# Schematic.net
KiCad netlist of a schematic drawn in EasyEDA
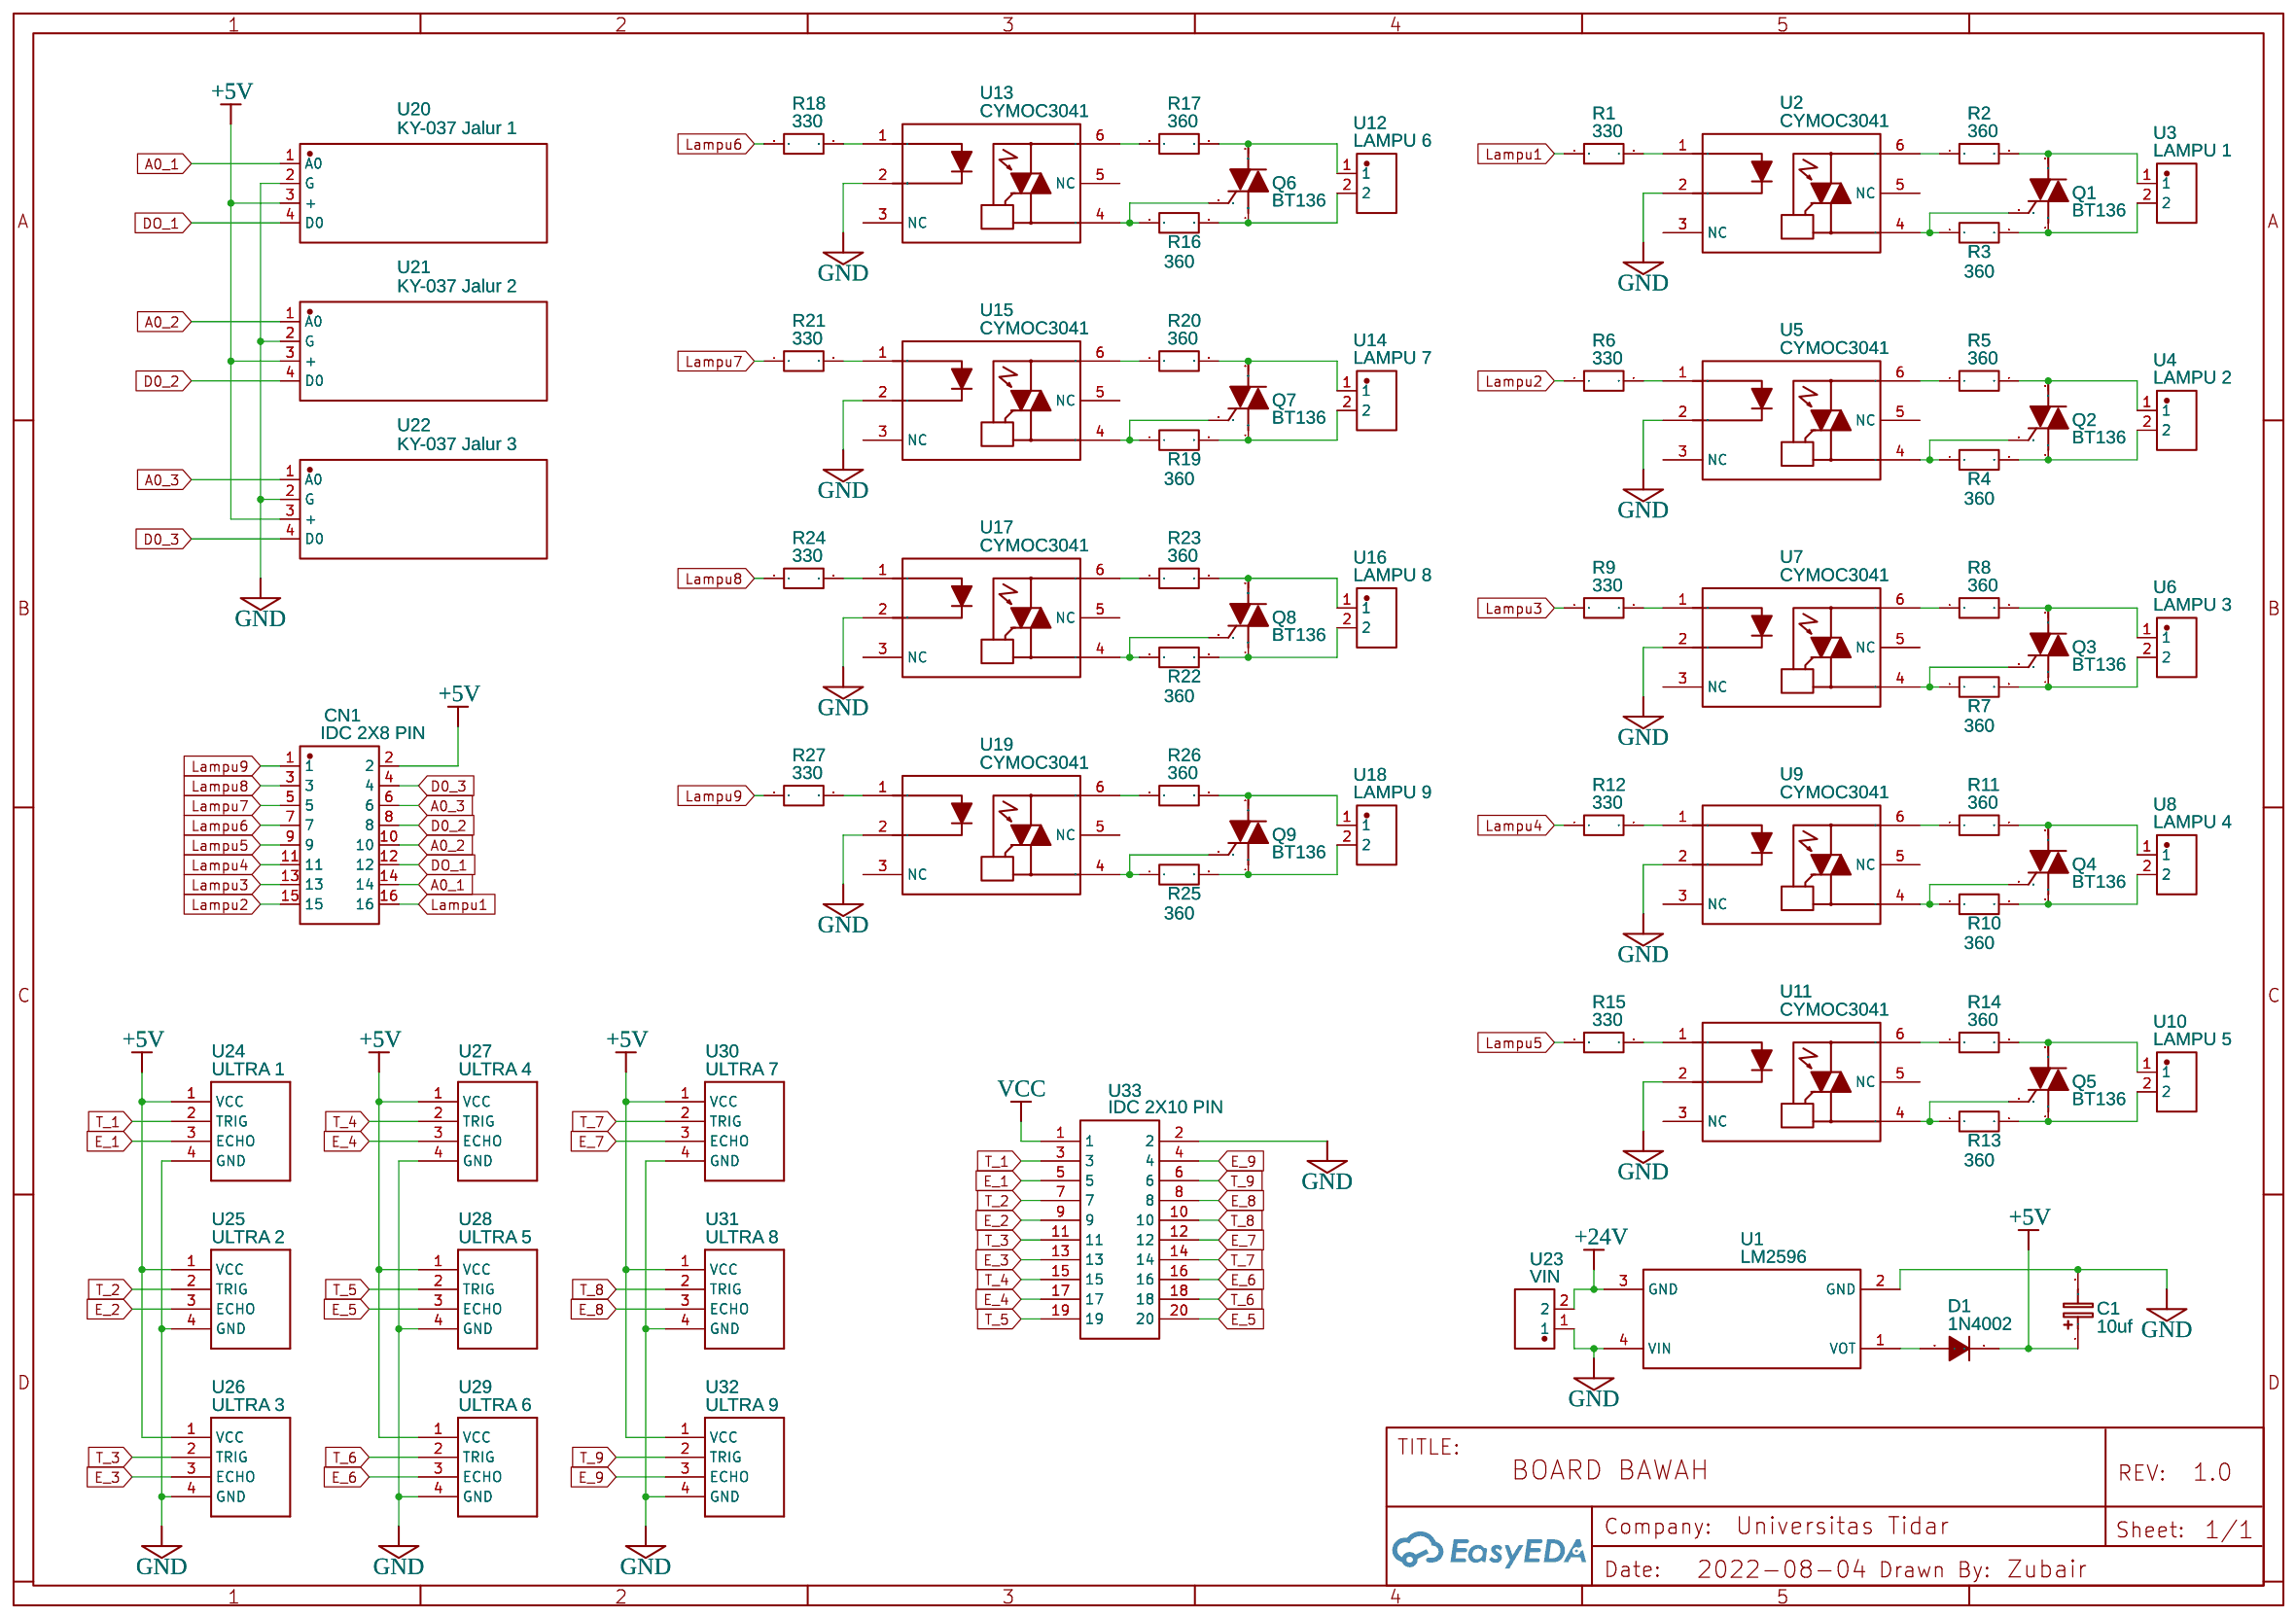
[diagram p0: BOARD BAWAH]
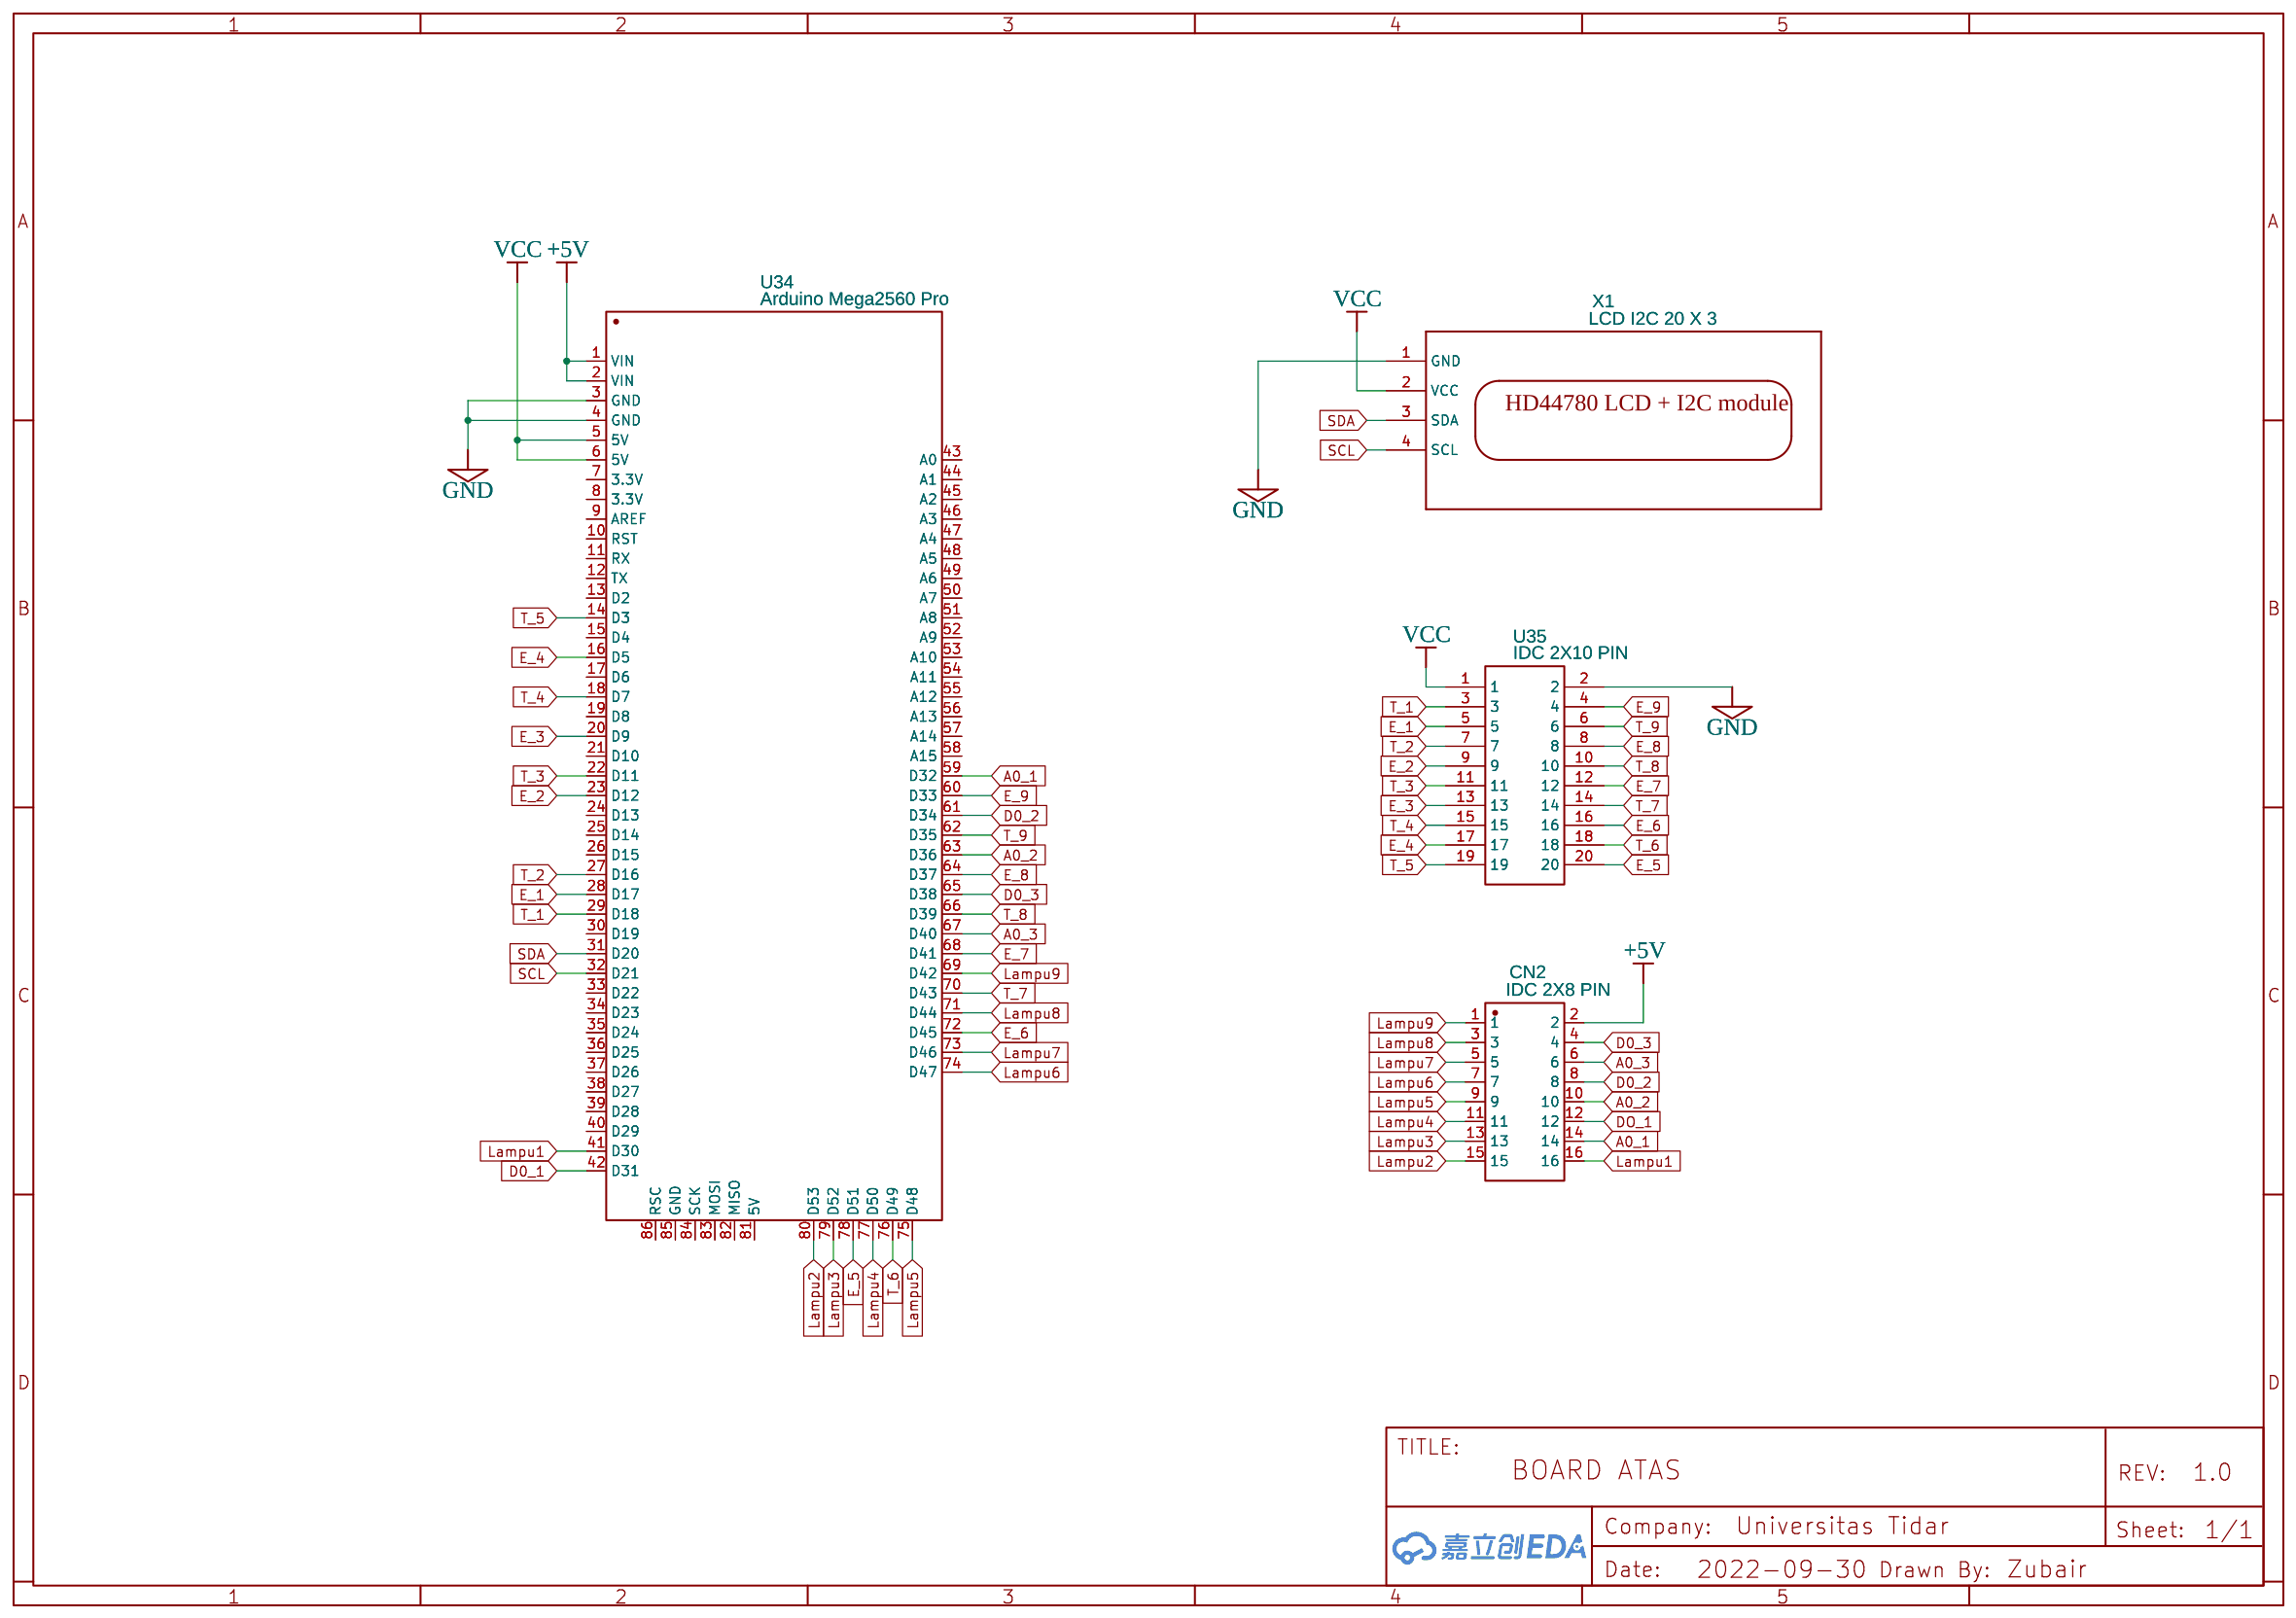
[diagram p1: BOARD ATAS]

(export (version "E")
  (design (tool "Eeschema 10.0.6"))
  (components
    (comp (ref "C1") (value "10uf") (libsource (lib "") (part "CE_TH_D5.0×F2.0_EU")))
    (comp (ref "CN1")
      (value "IDC 2X8 PIN")
      (fields
        (field (name "BOM_Manufacturer Part") "DW254P-2X8-L0")
        (field (name "BOM_Supplier Part") "C4749189")
      )
      (libsource (lib "") (part "DW254P-2X8-L0"))
    )
    (comp (ref "D1") (value "1N4002") (libsource (lib "") (part "1N4002")))
    (comp (ref "Q1")
      (value "BT136")
      (fields (field (name "BOM_Supplier Part") "C98796"))
      (libsource (lib "") (part "BT136"))
    )
    (comp (ref "Q2")
      (value "BT136")
      (fields (field (name "BOM_Supplier Part") "C98796"))
      (libsource (lib "") (part "BT136"))
    )
    (comp (ref "Q3")
      (value "BT136")
      (fields (field (name "BOM_Supplier Part") "C98796"))
      (libsource (lib "") (part "BT136"))
    )
    (comp (ref "Q4")
      (value "BT136")
      (fields (field (name "BOM_Supplier Part") "C98796"))
      (libsource (lib "") (part "BT136"))
    )
    (comp (ref "Q5")
      (value "BT136")
      (fields (field (name "BOM_Supplier Part") "C98796"))
      (libsource (lib "") (part "BT136"))
    )
    (comp (ref "Q6")
      (value "BT136")
      (fields (field (name "BOM_Supplier Part") "C98796"))
      (libsource (lib "") (part "BT136"))
    )
    (comp (ref "Q7")
      (value "BT136")
      (fields (field (name "BOM_Supplier Part") "C98796"))
      (libsource (lib "") (part "BT136"))
    )
    (comp (ref "Q8")
      (value "BT136")
      (fields (field (name "BOM_Supplier Part") "C98796"))
      (libsource (lib "") (part "BT136"))
    )
    (comp (ref "Q9")
      (value "BT136")
      (fields (field (name "BOM_Supplier Part") "C98796"))
      (libsource (lib "") (part "BT136"))
    )
    (comp (ref "R1")
      (value "330")
      (fields
        (field (name "BOM_Manufacturer Part") "贴片电阻ChipResistors")
        (field (name "BOM_Supplier Part") "C9900014833")
      )
      (libsource (lib "") (part "贴片电阻CHIPRESISTORS"))
    )
    (comp (ref "R2")
      (value "360")
      (fields
        (field (name "BOM_Manufacturer Part") "贴片电阻ChipResistors")
        (field (name "BOM_Supplier Part") "C9900014833")
      )
      (libsource (lib "") (part "贴片电阻CHIPRESISTORS"))
    )
    (comp (ref "R3")
      (value "360")
      (fields
        (field (name "BOM_Manufacturer Part") "贴片电阻ChipResistors")
        (field (name "BOM_Supplier Part") "C9900014833")
      )
      (libsource (lib "") (part "贴片电阻CHIPRESISTORS"))
    )
    (comp (ref "R4")
      (value "360")
      (fields
        (field (name "BOM_Manufacturer Part") "贴片电阻ChipResistors")
        (field (name "BOM_Supplier Part") "C9900014833")
      )
      (libsource (lib "") (part "贴片电阻CHIPRESISTORS"))
    )
    (comp (ref "R5")
      (value "360")
      (fields
        (field (name "BOM_Manufacturer Part") "贴片电阻ChipResistors")
        (field (name "BOM_Supplier Part") "C9900014833")
      )
      (libsource (lib "") (part "贴片电阻CHIPRESISTORS"))
    )
    (comp (ref "R6")
      (value "330")
      (fields
        (field (name "BOM_Manufacturer Part") "贴片电阻ChipResistors")
        (field (name "BOM_Supplier Part") "C9900014833")
      )
      (libsource (lib "") (part "贴片电阻CHIPRESISTORS"))
    )
    (comp (ref "R7")
      (value "360")
      (fields
        (field (name "BOM_Manufacturer Part") "贴片电阻ChipResistors")
        (field (name "BOM_Supplier Part") "C9900014833")
      )
      (libsource (lib "") (part "贴片电阻CHIPRESISTORS"))
    )
    (comp (ref "R8")
      (value "360")
      (fields
        (field (name "BOM_Manufacturer Part") "贴片电阻ChipResistors")
        (field (name "BOM_Supplier Part") "C9900014833")
      )
      (libsource (lib "") (part "贴片电阻CHIPRESISTORS"))
    )
    (comp (ref "R9")
      (value "330")
      (fields
        (field (name "BOM_Manufacturer Part") "贴片电阻ChipResistors")
        (field (name "BOM_Supplier Part") "C9900014833")
      )
      (libsource (lib "") (part "贴片电阻CHIPRESISTORS"))
    )
    (comp (ref "R10")
      (value "360")
      (fields
        (field (name "BOM_Manufacturer Part") "贴片电阻ChipResistors")
        (field (name "BOM_Supplier Part") "C9900014833")
      )
      (libsource (lib "") (part "贴片电阻CHIPRESISTORS"))
    )
    (comp (ref "R11")
      (value "360")
      (fields
        (field (name "BOM_Manufacturer Part") "贴片电阻ChipResistors")
        (field (name "BOM_Supplier Part") "C9900014833")
      )
      (libsource (lib "") (part "贴片电阻CHIPRESISTORS"))
    )
    (comp (ref "R12")
      (value "330")
      (fields
        (field (name "BOM_Manufacturer Part") "贴片电阻ChipResistors")
        (field (name "BOM_Supplier Part") "C9900014833")
      )
      (libsource (lib "") (part "贴片电阻CHIPRESISTORS"))
    )
    (comp (ref "R13")
      (value "360")
      (fields
        (field (name "BOM_Manufacturer Part") "贴片电阻ChipResistors")
        (field (name "BOM_Supplier Part") "C9900014833")
      )
      (libsource (lib "") (part "贴片电阻CHIPRESISTORS"))
    )
    (comp (ref "R14")
      (value "360")
      (fields
        (field (name "BOM_Manufacturer Part") "贴片电阻ChipResistors")
        (field (name "BOM_Supplier Part") "C9900014833")
      )
      (libsource (lib "") (part "贴片电阻CHIPRESISTORS"))
    )
    (comp (ref "R15")
      (value "330")
      (fields
        (field (name "BOM_Manufacturer Part") "贴片电阻ChipResistors")
        (field (name "BOM_Supplier Part") "C9900014833")
      )
      (libsource (lib "") (part "贴片电阻CHIPRESISTORS"))
    )
    (comp (ref "R16")
      (value "360")
      (fields
        (field (name "BOM_Manufacturer Part") "贴片电阻ChipResistors")
        (field (name "BOM_Supplier Part") "C9900014833")
      )
      (libsource (lib "") (part "贴片电阻CHIPRESISTORS"))
    )
    (comp (ref "R17")
      (value "360")
      (fields
        (field (name "BOM_Manufacturer Part") "贴片电阻ChipResistors")
        (field (name "BOM_Supplier Part") "C9900014833")
      )
      (libsource (lib "") (part "贴片电阻CHIPRESISTORS"))
    )
    (comp (ref "R18")
      (value "330")
      (fields
        (field (name "BOM_Manufacturer Part") "贴片电阻ChipResistors")
        (field (name "BOM_Supplier Part") "C9900014833")
      )
      (libsource (lib "") (part "贴片电阻CHIPRESISTORS"))
    )
    (comp (ref "R19")
      (value "360")
      (fields
        (field (name "BOM_Manufacturer Part") "贴片电阻ChipResistors")
        (field (name "BOM_Supplier Part") "C9900014833")
      )
      (libsource (lib "") (part "贴片电阻CHIPRESISTORS"))
    )
    (comp (ref "R20")
      (value "360")
      (fields
        (field (name "BOM_Manufacturer Part") "贴片电阻ChipResistors")
        (field (name "BOM_Supplier Part") "C9900014833")
      )
      (libsource (lib "") (part "贴片电阻CHIPRESISTORS"))
    )
    (comp (ref "R21")
      (value "330")
      (fields
        (field (name "BOM_Manufacturer Part") "贴片电阻ChipResistors")
        (field (name "BOM_Supplier Part") "C9900014833")
      )
      (libsource (lib "") (part "贴片电阻CHIPRESISTORS"))
    )
    (comp (ref "R22")
      (value "360")
      (fields
        (field (name "BOM_Manufacturer Part") "贴片电阻ChipResistors")
        (field (name "BOM_Supplier Part") "C9900014833")
      )
      (libsource (lib "") (part "贴片电阻CHIPRESISTORS"))
    )
    (comp (ref "R23")
      (value "360")
      (fields
        (field (name "BOM_Manufacturer Part") "贴片电阻ChipResistors")
        (field (name "BOM_Supplier Part") "C9900014833")
      )
      (libsource (lib "") (part "贴片电阻CHIPRESISTORS"))
    )
    (comp (ref "R24")
      (value "330")
      (fields
        (field (name "BOM_Manufacturer Part") "贴片电阻ChipResistors")
        (field (name "BOM_Supplier Part") "C9900014833")
      )
      (libsource (lib "") (part "贴片电阻CHIPRESISTORS"))
    )
    (comp (ref "R25")
      (value "360")
      (fields
        (field (name "BOM_Manufacturer Part") "贴片电阻ChipResistors")
        (field (name "BOM_Supplier Part") "C9900014833")
      )
      (libsource (lib "") (part "贴片电阻CHIPRESISTORS"))
    )
    (comp (ref "R26")
      (value "360")
      (fields
        (field (name "BOM_Manufacturer Part") "贴片电阻ChipResistors")
        (field (name "BOM_Supplier Part") "C9900014833")
      )
      (libsource (lib "") (part "贴片电阻CHIPRESISTORS"))
    )
    (comp (ref "R27")
      (value "330")
      (fields
        (field (name "BOM_Manufacturer Part") "贴片电阻ChipResistors")
        (field (name "BOM_Supplier Part") "C9900014833")
      )
      (libsource (lib "") (part "贴片电阻CHIPRESISTORS"))
    )
    (comp (ref "U1") (value "LM2596") (libsource (lib "") (part "LM2596")))
    (comp (ref "U2")
      (value "CYMOC3041")
      (fields (field (name "BOM_Supplier Part") "C3018797"))
      (libsource (lib "") (part "CYMOC3041"))
    )
    (comp (ref "U3")
      (value "LAMPU 1")
      (fields
        (field (name "BOM_Manufacturer Part") "DB128V-7.62-2P-GN-S")
        (field (name "BOM_Supplier Part") "C2686074")
      )
      (libsource (lib "") (part "DB128V-7.62-2P-GN-S"))
    )
    (comp (ref "U4")
      (value "LAMPU 2")
      (fields
        (field (name "BOM_Manufacturer Part") "DB128V-7.62-2P-GN-S")
        (field (name "BOM_Supplier Part") "C2686074")
      )
      (libsource (lib "") (part "DB128V-7.62-2P-GN-S"))
    )
    (comp (ref "U5")
      (value "CYMOC3041")
      (fields (field (name "BOM_Supplier Part") "C3018797"))
      (libsource (lib "") (part "CYMOC3041"))
    )
    (comp (ref "U6")
      (value "LAMPU 3")
      (fields
        (field (name "BOM_Manufacturer Part") "DB128V-7.62-2P-GN-S")
        (field (name "BOM_Supplier Part") "C2686074")
      )
      (libsource (lib "") (part "DB128V-7.62-2P-GN-S"))
    )
    (comp (ref "U7")
      (value "CYMOC3041")
      (fields (field (name "BOM_Supplier Part") "C3018797"))
      (libsource (lib "") (part "CYMOC3041"))
    )
    (comp (ref "U8")
      (value "LAMPU 4")
      (fields
        (field (name "BOM_Manufacturer Part") "DB128V-7.62-2P-GN-S")
        (field (name "BOM_Supplier Part") "C2686074")
      )
      (libsource (lib "") (part "DB128V-7.62-2P-GN-S"))
    )
    (comp (ref "U9")
      (value "CYMOC3041")
      (fields (field (name "BOM_Supplier Part") "C3018797"))
      (libsource (lib "") (part "CYMOC3041"))
    )
    (comp (ref "U10")
      (value "LAMPU 5")
      (fields
        (field (name "BOM_Manufacturer Part") "DB128V-7.62-2P-GN-S")
        (field (name "BOM_Supplier Part") "C2686074")
      )
      (libsource (lib "") (part "DB128V-7.62-2P-GN-S"))
    )
    (comp (ref "U11")
      (value "CYMOC3041")
      (fields (field (name "BOM_Supplier Part") "C3018797"))
      (libsource (lib "") (part "CYMOC3041"))
    )
    (comp (ref "U12")
      (value "LAMPU 6")
      (fields
        (field (name "BOM_Manufacturer Part") "DB128V-7.62-2P-GN-S")
        (field (name "BOM_Supplier Part") "C2686074")
      )
      (libsource (lib "") (part "DB128V-7.62-2P-GN-S"))
    )
    (comp (ref "U13")
      (value "CYMOC3041")
      (fields (field (name "BOM_Supplier Part") "C3018797"))
      (libsource (lib "") (part "CYMOC3041"))
    )
    (comp (ref "U14")
      (value "LAMPU 7")
      (fields
        (field (name "BOM_Manufacturer Part") "DB128V-7.62-2P-GN-S")
        (field (name "BOM_Supplier Part") "C2686074")
      )
      (libsource (lib "") (part "DB128V-7.62-2P-GN-S"))
    )
    (comp (ref "U15")
      (value "CYMOC3041")
      (fields (field (name "BOM_Supplier Part") "C3018797"))
      (libsource (lib "") (part "CYMOC3041"))
    )
    (comp (ref "U16")
      (value "LAMPU 8")
      (fields
        (field (name "BOM_Manufacturer Part") "DB128V-7.62-2P-GN-S")
        (field (name "BOM_Supplier Part") "C2686074")
      )
      (libsource (lib "") (part "DB128V-7.62-2P-GN-S"))
    )
    (comp (ref "U17")
      (value "CYMOC3041")
      (fields (field (name "BOM_Supplier Part") "C3018797"))
      (libsource (lib "") (part "CYMOC3041"))
    )
    (comp (ref "U18")
      (value "LAMPU 9")
      (fields
        (field (name "BOM_Manufacturer Part") "DB128V-7.62-2P-GN-S")
        (field (name "BOM_Supplier Part") "C2686074")
      )
      (libsource (lib "") (part "DB128V-7.62-2P-GN-S"))
    )
    (comp (ref "U19")
      (value "CYMOC3041")
      (fields (field (name "BOM_Supplier Part") "C3018797"))
      (libsource (lib "") (part "CYMOC3041"))
    )
    (comp (ref "U20")
      (value "KY-037 Jalur 1")
      (fields (field (name "BOM_Supplier Part") "420301"))
      (libsource (lib "") (part "KY-037 Geräuschsensor"))
    )
    (comp (ref "U21")
      (value "KY-037 Jalur 2")
      (fields (field (name "BOM_Supplier Part") "420301"))
      (libsource (lib "") (part "KY-037 Geräuschsensor"))
    )
    (comp (ref "U22")
      (value "KY-037 Jalur 3")
      (fields (field (name "BOM_Supplier Part") "420301"))
      (libsource (lib "") (part "KY-037 Geräuschsensor"))
    )
    (comp (ref "U23")
      (value "VIN")
      (fields
        (field (name "BOM_Manufacturer Part") "DB128V-7.62-2P-GN-S")
        (field (name "BOM_Supplier Part") "C2686074")
      )
      (libsource (lib "") (part "DB128V-7.62-2P-GN-S_1"))
    )
    (comp (ref "U24") (value "ULTRA 1") (libsource (lib "") (part "ULTRASONIC-HC-SR04 COPY")))
    (comp (ref "U25") (value "ULTRA 2") (libsource (lib "") (part "ULTRASONIC-HC-SR04 COPY")))
    (comp (ref "U26") (value "ULTRA 3") (libsource (lib "") (part "ULTRASONIC-HC-SR04 COPY")))
    (comp (ref "U27") (value "ULTRA 4") (libsource (lib "") (part "ULTRASONIC-HC-SR04 COPY")))
    (comp (ref "U28") (value "ULTRA 5") (libsource (lib "") (part "ULTRASONIC-HC-SR04 COPY")))
    (comp (ref "U29") (value "ULTRA 6") (libsource (lib "") (part "ULTRASONIC-HC-SR04 COPY")))
    (comp (ref "U30") (value "ULTRA 7") (libsource (lib "") (part "ULTRASONIC-HC-SR04 COPY")))
    (comp (ref "U31") (value "ULTRA 8") (libsource (lib "") (part "ULTRASONIC-HC-SR04 COPY")))
    (comp (ref "U32") (value "ULTRA 9") (libsource (lib "") (part "ULTRASONIC-HC-SR04 COPY")))
    (comp (ref "U33")
      (value "IDC 2X10 PIN")
      (fields
        (field (name "BOM_Manufacturer Part") "2*10P牛角插座")
        (field (name "BOM_Supplier Part") "C9900014220")
      )
      (libsource (lib "") (part "2*10P牛角插座"))
    )
    (comp (ref "CN2")
      (value "IDC 2X8 PIN")
      (fields
        (field (name "BOM_Manufacturer Part") "DW254P-2X8-L0")
        (field (name "BOM_Supplier Part") "C4749189")
      )
      (libsource (lib "") (part "DW254P-2X8-L0"))
    )
    (comp (ref "U34") (value "Arduino Mega2560 Pro") (libsource (lib "") (part "Arduino Mega2560 Pro")))
    (comp (ref "U35")
      (value "IDC 2X10 PIN")
      (fields
        (field (name "BOM_Manufacturer Part") "2*10P牛角插座")
        (field (name "BOM_Supplier Part") "C9900014220")
      )
      (libsource (lib "") (part "2*10P牛角插座"))
    )
    (comp (ref "X1")
      (value "LCD I2C 20 X 3")
      (libsource (lib "") (part "SCREEN LCD HD44780LCD WITH I2C MODULE"))
    )
  )
  (nets
    (net (code "1") (name "+5V") (class "Default")
      (node (ref "C1") (pin "1") (pinfunction "1_1") (pintype "unspecified"))
      (node (ref "CN1") (pin "2") (pinfunction "2_2") (pintype "unspecified"))
      (node (ref "CN2") (pin "2") (pinfunction "2_2") (pintype "unspecified"))
      (node (ref "D1") (pin "1") (pinfunction "K_1") (pintype "unspecified"))
      (node (ref "U20") (pin "3") (pinfunction "+_3") (pintype "unspecified"))
      (node (ref "U21") (pin "3") (pinfunction "+_3") (pintype "unspecified"))
      (node (ref "U22") (pin "3") (pinfunction "+_3") (pintype "unspecified"))
      (node (ref "U24") (pin "1") (pinfunction "VCC_1") (pintype "passive"))
      (node (ref "U25") (pin "1") (pinfunction "VCC_1") (pintype "passive"))
      (node (ref "U26") (pin "1") (pinfunction "VCC_1") (pintype "passive"))
      (node (ref "U27") (pin "1") (pinfunction "VCC_1") (pintype "passive"))
      (node (ref "U28") (pin "1") (pinfunction "VCC_1") (pintype "passive"))
      (node (ref "U29") (pin "1") (pinfunction "VCC_1") (pintype "passive"))
      (node (ref "U30") (pin "1") (pinfunction "VCC_1") (pintype "passive"))
      (node (ref "U31") (pin "1") (pinfunction "VCC_1") (pintype "passive"))
      (node (ref "U32") (pin "1") (pinfunction "VCC_1") (pintype "passive"))
      (node (ref "U34") (pin "1") (pinfunction "VIN_1") (pintype "unspecified"))
      (node (ref "U34") (pin "2") (pinfunction "VIN_2") (pintype "unspecified"))
    )
    (net (code "2") (name "+24V") (class "Default")
      (node (ref "U1") (pin "3") (pinfunction "GND_3") (pintype "unspecified"))
      (node (ref "U23") (pin "2") (pinfunction "2_2") (pintype "unspecified"))
    )
    (net (code "3") (name "A0_1") (class "Default")
      (node (ref "CN1") (pin "14") (pinfunction "14_14") (pintype "unspecified"))
      (node (ref "CN2") (pin "14") (pinfunction "14_14") (pintype "unspecified"))
      (node (ref "U20") (pin "1") (pinfunction "A0_1") (pintype "unspecified"))
      (node (ref "U34") (pin "59") (pinfunction "D32_59") (pintype "unspecified"))
    )
    (net (code "4") (name "A0_2") (class "Default")
      (node (ref "CN1") (pin "10") (pinfunction "10_10") (pintype "unspecified"))
      (node (ref "CN2") (pin "10") (pinfunction "10_10") (pintype "unspecified"))
      (node (ref "U21") (pin "1") (pinfunction "A0_1") (pintype "unspecified"))
      (node (ref "U34") (pin "63") (pinfunction "D36_63") (pintype "unspecified"))
    )
    (net (code "5") (name "A0_3") (class "Default")
      (node (ref "CN1") (pin "6") (pinfunction "6_6") (pintype "unspecified"))
      (node (ref "CN2") (pin "6") (pinfunction "6_6") (pintype "unspecified"))
      (node (ref "U22") (pin "1") (pinfunction "A0_1") (pintype "unspecified"))
      (node (ref "U34") (pin "67") (pinfunction "D40_67") (pintype "unspecified"))
    )
    (net (code "6") (name "D0_1") (class "Default")
      (node (ref "U34") (pin "42") (pinfunction "D31_42") (pintype "unspecified"))
    )
    (net (code "7") (name "D0_2") (class "Default")
      (node (ref "CN1") (pin "8") (pinfunction "8_8") (pintype "unspecified"))
      (node (ref "CN2") (pin "8") (pinfunction "8_8") (pintype "unspecified"))
      (node (ref "U21") (pin "4") (pinfunction "D0_4") (pintype "unspecified"))
      (node (ref "U34") (pin "61") (pinfunction "D34_61") (pintype "unspecified"))
    )
    (net (code "8") (name "D0_3") (class "Default")
      (node (ref "CN1") (pin "4") (pinfunction "4_4") (pintype "unspecified"))
      (node (ref "CN2") (pin "4") (pinfunction "4_4") (pintype "unspecified"))
      (node (ref "U22") (pin "4") (pinfunction "D0_4") (pintype "unspecified"))
      (node (ref "U34") (pin "65") (pinfunction "D38_65") (pintype "unspecified"))
    )
    (net (code "9") (name "DO_1") (class "Default")
      (node (ref "CN1") (pin "12") (pinfunction "12_12") (pintype "unspecified"))
      (node (ref "CN2") (pin "12") (pinfunction "12_12") (pintype "unspecified"))
      (node (ref "U20") (pin "4") (pinfunction "D0_4") (pintype "unspecified"))
    )
    (net (code "10") (name "E_1") (class "Default")
      (node (ref "U24") (pin "3") (pinfunction "ECHO_3") (pintype "output"))
      (node (ref "U33") (pin "5") (pinfunction "5_5") (pintype "unspecified"))
      (node (ref "U34") (pin "28") (pinfunction "D17_28") (pintype "unspecified"))
      (node (ref "U35") (pin "5") (pinfunction "5_5") (pintype "unspecified"))
    )
    (net (code "11") (name "E_2") (class "Default")
      (node (ref "U25") (pin "3") (pinfunction "ECHO_3") (pintype "output"))
      (node (ref "U33") (pin "9") (pinfunction "9_9") (pintype "unspecified"))
      (node (ref "U34") (pin "23") (pinfunction "D12_23") (pintype "unspecified"))
      (node (ref "U35") (pin "9") (pinfunction "9_9") (pintype "unspecified"))
    )
    (net (code "12") (name "E_3") (class "Default")
      (node (ref "U26") (pin "3") (pinfunction "ECHO_3") (pintype "output"))
      (node (ref "U33") (pin "13") (pinfunction "13_13") (pintype "unspecified"))
      (node (ref "U34") (pin "20") (pinfunction "D9_20") (pintype "unspecified"))
      (node (ref "U35") (pin "13") (pinfunction "13_13") (pintype "unspecified"))
    )
    (net (code "13") (name "E_4") (class "Default")
      (node (ref "U27") (pin "3") (pinfunction "ECHO_3") (pintype "output"))
      (node (ref "U33") (pin "17") (pinfunction "17_17") (pintype "unspecified"))
      (node (ref "U34") (pin "16") (pinfunction "D5_16") (pintype "unspecified"))
      (node (ref "U35") (pin "17") (pinfunction "17_17") (pintype "unspecified"))
    )
    (net (code "14") (name "E_5") (class "Default")
      (node (ref "U28") (pin "3") (pinfunction "ECHO_3") (pintype "output"))
      (node (ref "U33") (pin "20") (pinfunction "20_20") (pintype "unspecified"))
      (node (ref "U34") (pin "78") (pinfunction "D51_78") (pintype "unspecified"))
      (node (ref "U35") (pin "20") (pinfunction "20_20") (pintype "unspecified"))
    )
    (net (code "15") (name "E_6") (class "Default")
      (node (ref "U29") (pin "3") (pinfunction "ECHO_3") (pintype "output"))
      (node (ref "U33") (pin "16") (pinfunction "16_16") (pintype "unspecified"))
      (node (ref "U34") (pin "72") (pinfunction "D45_72") (pintype "unspecified"))
      (node (ref "U35") (pin "16") (pinfunction "16_16") (pintype "unspecified"))
    )
    (net (code "16") (name "E_7") (class "Default")
      (node (ref "U30") (pin "3") (pinfunction "ECHO_3") (pintype "output"))
      (node (ref "U33") (pin "12") (pinfunction "12_12") (pintype "unspecified"))
      (node (ref "U34") (pin "68") (pinfunction "D41_68") (pintype "unspecified"))
      (node (ref "U35") (pin "12") (pinfunction "12_12") (pintype "unspecified"))
    )
    (net (code "17") (name "E_8") (class "Default")
      (node (ref "U31") (pin "3") (pinfunction "ECHO_3") (pintype "output"))
      (node (ref "U33") (pin "8") (pinfunction "8_8") (pintype "unspecified"))
      (node (ref "U34") (pin "64") (pinfunction "D37_64") (pintype "unspecified"))
      (node (ref "U35") (pin "8") (pinfunction "8_8") (pintype "unspecified"))
    )
    (net (code "18") (name "E_9") (class "Default")
      (node (ref "U32") (pin "3") (pinfunction "ECHO_3") (pintype "output"))
      (node (ref "U33") (pin "4") (pinfunction "4_4") (pintype "unspecified"))
      (node (ref "U34") (pin "60") (pinfunction "D33_60") (pintype "unspecified"))
      (node (ref "U35") (pin "4") (pinfunction "4_4") (pintype "unspecified"))
    )
    (net (code "19") (name "GND") (class "Default")
      (node (ref "C1") (pin "2") (pinfunction "2_2") (pintype "unspecified"))
      (node (ref "U1") (pin "2") (pinfunction "GND_2") (pintype "unspecified"))
      (node (ref "U1") (pin "4") (pinfunction "VIN_4") (pintype "unspecified"))
      (node (ref "U11") (pin "2") (pinfunction "CAT_2") (pintype "unspecified"))
      (node (ref "U13") (pin "2") (pinfunction "CAT_2") (pintype "unspecified"))
      (node (ref "U15") (pin "2") (pinfunction "CAT_2") (pintype "unspecified"))
      (node (ref "U17") (pin "2") (pinfunction "CAT_2") (pintype "unspecified"))
      (node (ref "U19") (pin "2") (pinfunction "CAT_2") (pintype "unspecified"))
      (node (ref "U2") (pin "2") (pinfunction "CAT_2") (pintype "unspecified"))
      (node (ref "U20") (pin "2") (pinfunction "G_2") (pintype "unspecified"))
      (node (ref "U21") (pin "2") (pinfunction "G_2") (pintype "unspecified"))
      (node (ref "U22") (pin "2") (pinfunction "G_2") (pintype "unspecified"))
      (node (ref "U23") (pin "1") (pinfunction "1_1") (pintype "unspecified"))
      (node (ref "U24") (pin "4") (pinfunction "GND_4") (pintype "passive"))
      (node (ref "U25") (pin "4") (pinfunction "GND_4") (pintype "passive"))
      (node (ref "U26") (pin "4") (pinfunction "GND_4") (pintype "passive"))
      (node (ref "U27") (pin "4") (pinfunction "GND_4") (pintype "passive"))
      (node (ref "U28") (pin "4") (pinfunction "GND_4") (pintype "passive"))
      (node (ref "U29") (pin "4") (pinfunction "GND_4") (pintype "passive"))
      (node (ref "U30") (pin "4") (pinfunction "GND_4") (pintype "passive"))
      (node (ref "U31") (pin "4") (pinfunction "GND_4") (pintype "passive"))
      (node (ref "U32") (pin "4") (pinfunction "GND_4") (pintype "passive"))
      (node (ref "U33") (pin "2") (pinfunction "2_2") (pintype "unspecified"))
      (node (ref "U34") (pin "3") (pinfunction "GND_3") (pintype "unspecified"))
      (node (ref "U34") (pin "4") (pinfunction "GND_4") (pintype "unspecified"))
      (node (ref "U35") (pin "2") (pinfunction "2_2") (pintype "unspecified"))
      (node (ref "U5") (pin "2") (pinfunction "CAT_2") (pintype "unspecified"))
      (node (ref "U7") (pin "2") (pinfunction "CAT_2") (pintype "unspecified"))
      (node (ref "U9") (pin "2") (pinfunction "CAT_2") (pintype "unspecified"))
      (node (ref "X1") (pin "1") (pinfunction "GND_1") (pintype "unspecified"))
    )
    (net (code "20") (name "Lampu1") (class "Default")
      (node (ref "CN1") (pin "16") (pinfunction "16_16") (pintype "unspecified"))
      (node (ref "CN2") (pin "16") (pinfunction "16_16") (pintype "unspecified"))
      (node (ref "R1") (pin "1") (pinfunction "1_1") (pintype "unspecified"))
      (node (ref "U34") (pin "41") (pinfunction "D30_41") (pintype "unspecified"))
    )
    (net (code "21") (name "Lampu2") (class "Default")
      (node (ref "CN1") (pin "15") (pinfunction "15_15") (pintype "unspecified"))
      (node (ref "CN2") (pin "15") (pinfunction "15_15") (pintype "unspecified"))
      (node (ref "R6") (pin "1") (pinfunction "1_1") (pintype "unspecified"))
      (node (ref "U34") (pin "80") (pinfunction "D53_80") (pintype "unspecified"))
    )
    (net (code "22") (name "Lampu3") (class "Default")
      (node (ref "CN1") (pin "13") (pinfunction "13_13") (pintype "unspecified"))
      (node (ref "CN2") (pin "13") (pinfunction "13_13") (pintype "unspecified"))
      (node (ref "R9") (pin "1") (pinfunction "1_1") (pintype "unspecified"))
      (node (ref "U34") (pin "79") (pinfunction "D52_79") (pintype "unspecified"))
    )
    (net (code "23") (name "Lampu4") (class "Default")
      (node (ref "CN1") (pin "11") (pinfunction "11_11") (pintype "unspecified"))
      (node (ref "CN2") (pin "11") (pinfunction "11_11") (pintype "unspecified"))
      (node (ref "R12") (pin "1") (pinfunction "1_1") (pintype "unspecified"))
      (node (ref "U34") (pin "77") (pinfunction "D50_77") (pintype "unspecified"))
    )
    (net (code "24") (name "Lampu5") (class "Default")
      (node (ref "CN1") (pin "9") (pinfunction "9_9") (pintype "unspecified"))
      (node (ref "CN2") (pin "9") (pinfunction "9_9") (pintype "unspecified"))
      (node (ref "R15") (pin "1") (pinfunction "1_1") (pintype "unspecified"))
      (node (ref "U34") (pin "75") (pinfunction "D48_75") (pintype "unspecified"))
    )
    (net (code "25") (name "Lampu6") (class "Default")
      (node (ref "CN1") (pin "7") (pinfunction "7_7") (pintype "unspecified"))
      (node (ref "CN2") (pin "7") (pinfunction "7_7") (pintype "unspecified"))
      (node (ref "R18") (pin "1") (pinfunction "1_1") (pintype "unspecified"))
      (node (ref "U34") (pin "74") (pinfunction "D47_74") (pintype "unspecified"))
    )
    (net (code "26") (name "Lampu7") (class "Default")
      (node (ref "CN1") (pin "5") (pinfunction "5_5") (pintype "unspecified"))
      (node (ref "CN2") (pin "5") (pinfunction "5_5") (pintype "unspecified"))
      (node (ref "R21") (pin "1") (pinfunction "1_1") (pintype "unspecified"))
      (node (ref "U34") (pin "73") (pinfunction "D46_73") (pintype "unspecified"))
    )
    (net (code "27") (name "Lampu8") (class "Default")
      (node (ref "CN1") (pin "3") (pinfunction "3_3") (pintype "unspecified"))
      (node (ref "CN2") (pin "3") (pinfunction "3_3") (pintype "unspecified"))
      (node (ref "R24") (pin "1") (pinfunction "1_1") (pintype "unspecified"))
      (node (ref "U34") (pin "71") (pinfunction "D44_71") (pintype "unspecified"))
    )
    (net (code "28") (name "Lampu9") (class "Default")
      (node (ref "CN1") (pin "1") (pinfunction "1_1") (pintype "unspecified"))
      (node (ref "CN2") (pin "1") (pinfunction "1_1") (pintype "unspecified"))
      (node (ref "R27") (pin "1") (pinfunction "1_1") (pintype "unspecified"))
      (node (ref "U34") (pin "69") (pinfunction "D42_69") (pintype "unspecified"))
    )
    (net (code "29") (name "Net-(D1-A)") (class "Default")
      (node (ref "D1") (pin "2") (pinfunction "A_2") (pintype "unspecified"))
      (node (ref "U1") (pin "1") (pinfunction "VOT_1") (pintype "unspecified"))
    )
    (net (code "30") (name "Net-(Q1-G)") (class "Default")
      (node (ref "Q1") (pin "3") (pinfunction "G_3") (pintype "unspecified"))
      (node (ref "R3") (pin "1") (pinfunction "1_1") (pintype "unspecified"))
      (node (ref "U2") (pin "4") (pinfunction "MT_4") (pintype "unspecified"))
    )
    (net (code "31") (name "Net-(Q1-M1)") (class "Default")
      (node (ref "Q1") (pin "1") (pinfunction "M1_1") (pintype "unspecified"))
      (node (ref "R3") (pin "2") (pinfunction "2_2") (pintype "unspecified"))
      (node (ref "U3") (pin "2") (pinfunction "2_2") (pintype "unspecified"))
    )
    (net (code "32") (name "Net-(Q1-M2)") (class "Default")
      (node (ref "Q1") (pin "2") (pinfunction "M2_2") (pintype "unspecified"))
      (node (ref "R2") (pin "2") (pinfunction "2_2") (pintype "unspecified"))
      (node (ref "U3") (pin "1") (pinfunction "1_1") (pintype "unspecified"))
    )
    (net (code "33") (name "Net-(Q2-G)") (class "Default")
      (node (ref "Q2") (pin "3") (pinfunction "G_3") (pintype "unspecified"))
      (node (ref "R4") (pin "1") (pinfunction "1_1") (pintype "unspecified"))
      (node (ref "U5") (pin "4") (pinfunction "MT_4") (pintype "unspecified"))
    )
    (net (code "34") (name "Net-(Q2-M1)") (class "Default")
      (node (ref "Q2") (pin "1") (pinfunction "M1_1") (pintype "unspecified"))
      (node (ref "R4") (pin "2") (pinfunction "2_2") (pintype "unspecified"))
      (node (ref "U4") (pin "2") (pinfunction "2_2") (pintype "unspecified"))
    )
    (net (code "35") (name "Net-(Q2-M2)") (class "Default")
      (node (ref "Q2") (pin "2") (pinfunction "M2_2") (pintype "unspecified"))
      (node (ref "R5") (pin "2") (pinfunction "2_2") (pintype "unspecified"))
      (node (ref "U4") (pin "1") (pinfunction "1_1") (pintype "unspecified"))
    )
    (net (code "36") (name "Net-(Q3-G)") (class "Default")
      (node (ref "Q3") (pin "3") (pinfunction "G_3") (pintype "unspecified"))
      (node (ref "R7") (pin "1") (pinfunction "1_1") (pintype "unspecified"))
      (node (ref "U7") (pin "4") (pinfunction "MT_4") (pintype "unspecified"))
    )
    (net (code "37") (name "Net-(Q3-M1)") (class "Default")
      (node (ref "Q3") (pin "1") (pinfunction "M1_1") (pintype "unspecified"))
      (node (ref "R7") (pin "2") (pinfunction "2_2") (pintype "unspecified"))
      (node (ref "U6") (pin "2") (pinfunction "2_2") (pintype "unspecified"))
    )
    (net (code "38") (name "Net-(Q3-M2)") (class "Default")
      (node (ref "Q3") (pin "2") (pinfunction "M2_2") (pintype "unspecified"))
      (node (ref "R8") (pin "2") (pinfunction "2_2") (pintype "unspecified"))
      (node (ref "U6") (pin "1") (pinfunction "1_1") (pintype "unspecified"))
    )
    (net (code "39") (name "Net-(Q4-G)") (class "Default")
      (node (ref "Q4") (pin "3") (pinfunction "G_3") (pintype "unspecified"))
      (node (ref "R10") (pin "1") (pinfunction "1_1") (pintype "unspecified"))
      (node (ref "U9") (pin "4") (pinfunction "MT_4") (pintype "unspecified"))
    )
    (net (code "40") (name "Net-(Q4-M1)") (class "Default")
      (node (ref "Q4") (pin "1") (pinfunction "M1_1") (pintype "unspecified"))
      (node (ref "R10") (pin "2") (pinfunction "2_2") (pintype "unspecified"))
      (node (ref "U8") (pin "2") (pinfunction "2_2") (pintype "unspecified"))
    )
    (net (code "41") (name "Net-(Q4-M2)") (class "Default")
      (node (ref "Q4") (pin "2") (pinfunction "M2_2") (pintype "unspecified"))
      (node (ref "R11") (pin "2") (pinfunction "2_2") (pintype "unspecified"))
      (node (ref "U8") (pin "1") (pinfunction "1_1") (pintype "unspecified"))
    )
    (net (code "42") (name "Net-(Q5-G)") (class "Default")
      (node (ref "Q5") (pin "3") (pinfunction "G_3") (pintype "unspecified"))
      (node (ref "R13") (pin "1") (pinfunction "1_1") (pintype "unspecified"))
      (node (ref "U11") (pin "4") (pinfunction "MT_4") (pintype "unspecified"))
    )
    (net (code "43") (name "Net-(Q5-M1)") (class "Default")
      (node (ref "Q5") (pin "1") (pinfunction "M1_1") (pintype "unspecified"))
      (node (ref "R13") (pin "2") (pinfunction "2_2") (pintype "unspecified"))
      (node (ref "U10") (pin "2") (pinfunction "2_2") (pintype "unspecified"))
    )
    (net (code "44") (name "Net-(Q5-M2)") (class "Default")
      (node (ref "Q5") (pin "2") (pinfunction "M2_2") (pintype "unspecified"))
      (node (ref "R14") (pin "2") (pinfunction "2_2") (pintype "unspecified"))
      (node (ref "U10") (pin "1") (pinfunction "1_1") (pintype "unspecified"))
    )
    (net (code "45") (name "Net-(Q6-G)") (class "Default")
      (node (ref "Q6") (pin "3") (pinfunction "G_3") (pintype "unspecified"))
      (node (ref "R16") (pin "1") (pinfunction "1_1") (pintype "unspecified"))
      (node (ref "U13") (pin "4") (pinfunction "MT_4") (pintype "unspecified"))
    )
    (net (code "46") (name "Net-(Q6-M1)") (class "Default")
      (node (ref "Q6") (pin "1") (pinfunction "M1_1") (pintype "unspecified"))
      (node (ref "R16") (pin "2") (pinfunction "2_2") (pintype "unspecified"))
      (node (ref "U12") (pin "2") (pinfunction "2_2") (pintype "unspecified"))
    )
    (net (code "47") (name "Net-(Q6-M2)") (class "Default")
      (node (ref "Q6") (pin "2") (pinfunction "M2_2") (pintype "unspecified"))
      (node (ref "R17") (pin "2") (pinfunction "2_2") (pintype "unspecified"))
      (node (ref "U12") (pin "1") (pinfunction "1_1") (pintype "unspecified"))
    )
    (net (code "48") (name "Net-(Q7-G)") (class "Default")
      (node (ref "Q7") (pin "3") (pinfunction "G_3") (pintype "unspecified"))
      (node (ref "R19") (pin "1") (pinfunction "1_1") (pintype "unspecified"))
      (node (ref "U15") (pin "4") (pinfunction "MT_4") (pintype "unspecified"))
    )
    (net (code "49") (name "Net-(Q7-M1)") (class "Default")
      (node (ref "Q7") (pin "1") (pinfunction "M1_1") (pintype "unspecified"))
      (node (ref "R19") (pin "2") (pinfunction "2_2") (pintype "unspecified"))
      (node (ref "U14") (pin "2") (pinfunction "2_2") (pintype "unspecified"))
    )
    (net (code "50") (name "Net-(Q7-M2)") (class "Default")
      (node (ref "Q7") (pin "2") (pinfunction "M2_2") (pintype "unspecified"))
      (node (ref "R20") (pin "2") (pinfunction "2_2") (pintype "unspecified"))
      (node (ref "U14") (pin "1") (pinfunction "1_1") (pintype "unspecified"))
    )
    (net (code "51") (name "Net-(Q8-G)") (class "Default")
      (node (ref "Q8") (pin "3") (pinfunction "G_3") (pintype "unspecified"))
      (node (ref "R22") (pin "1") (pinfunction "1_1") (pintype "unspecified"))
      (node (ref "U17") (pin "4") (pinfunction "MT_4") (pintype "unspecified"))
    )
    (net (code "52") (name "Net-(Q8-M1)") (class "Default")
      (node (ref "Q8") (pin "1") (pinfunction "M1_1") (pintype "unspecified"))
      (node (ref "R22") (pin "2") (pinfunction "2_2") (pintype "unspecified"))
      (node (ref "U16") (pin "2") (pinfunction "2_2") (pintype "unspecified"))
    )
    (net (code "53") (name "Net-(Q8-M2)") (class "Default")
      (node (ref "Q8") (pin "2") (pinfunction "M2_2") (pintype "unspecified"))
      (node (ref "R23") (pin "2") (pinfunction "2_2") (pintype "unspecified"))
      (node (ref "U16") (pin "1") (pinfunction "1_1") (pintype "unspecified"))
    )
    (net (code "54") (name "Net-(Q9-G)") (class "Default")
      (node (ref "Q9") (pin "3") (pinfunction "G_3") (pintype "unspecified"))
      (node (ref "R25") (pin "1") (pinfunction "1_1") (pintype "unspecified"))
      (node (ref "U19") (pin "4") (pinfunction "MT_4") (pintype "unspecified"))
    )
    (net (code "55") (name "Net-(Q9-M1)") (class "Default")
      (node (ref "Q9") (pin "1") (pinfunction "M1_1") (pintype "unspecified"))
      (node (ref "R25") (pin "2") (pinfunction "2_2") (pintype "unspecified"))
      (node (ref "U18") (pin "2") (pinfunction "2_2") (pintype "unspecified"))
    )
    (net (code "56") (name "Net-(Q9-M2)") (class "Default")
      (node (ref "Q9") (pin "2") (pinfunction "M2_2") (pintype "unspecified"))
      (node (ref "R26") (pin "2") (pinfunction "2_2") (pintype "unspecified"))
      (node (ref "U18") (pin "1") (pinfunction "1_1") (pintype "unspecified"))
    )
    (net (code "57") (name "Net-(R2-Pad1)") (class "Default")
      (node (ref "R2") (pin "1") (pinfunction "1_1") (pintype "unspecified"))
      (node (ref "U2") (pin "6") (pinfunction "MT_6") (pintype "unspecified"))
    )
    (net (code "58") (name "Net-(R5-Pad1)") (class "Default")
      (node (ref "R5") (pin "1") (pinfunction "1_1") (pintype "unspecified"))
      (node (ref "U5") (pin "6") (pinfunction "MT_6") (pintype "unspecified"))
    )
    (net (code "59") (name "Net-(R8-Pad1)") (class "Default")
      (node (ref "R8") (pin "1") (pinfunction "1_1") (pintype "unspecified"))
      (node (ref "U7") (pin "6") (pinfunction "MT_6") (pintype "unspecified"))
    )
    (net (code "60") (name "Net-(R11-Pad1)") (class "Default")
      (node (ref "R11") (pin "1") (pinfunction "1_1") (pintype "unspecified"))
      (node (ref "U9") (pin "6") (pinfunction "MT_6") (pintype "unspecified"))
    )
    (net (code "61") (name "Net-(R14-Pad1)") (class "Default")
      (node (ref "R14") (pin "1") (pinfunction "1_1") (pintype "unspecified"))
      (node (ref "U11") (pin "6") (pinfunction "MT_6") (pintype "unspecified"))
    )
    (net (code "62") (name "Net-(R17-Pad1)") (class "Default")
      (node (ref "R17") (pin "1") (pinfunction "1_1") (pintype "unspecified"))
      (node (ref "U13") (pin "6") (pinfunction "MT_6") (pintype "unspecified"))
    )
    (net (code "63") (name "Net-(R20-Pad1)") (class "Default")
      (node (ref "R20") (pin "1") (pinfunction "1_1") (pintype "unspecified"))
      (node (ref "U15") (pin "6") (pinfunction "MT_6") (pintype "unspecified"))
    )
    (net (code "64") (name "Net-(R23-Pad1)") (class "Default")
      (node (ref "R23") (pin "1") (pinfunction "1_1") (pintype "unspecified"))
      (node (ref "U17") (pin "6") (pinfunction "MT_6") (pintype "unspecified"))
    )
    (net (code "65") (name "Net-(R26-Pad1)") (class "Default")
      (node (ref "R26") (pin "1") (pinfunction "1_1") (pintype "unspecified"))
      (node (ref "U19") (pin "6") (pinfunction "MT_6") (pintype "unspecified"))
    )
    (net (code "66") (name "Net-(U2-AN)") (class "Default")
      (node (ref "R1") (pin "2") (pinfunction "2_2") (pintype "unspecified"))
      (node (ref "U2") (pin "1") (pinfunction "AN_1") (pintype "unspecified"))
    )
    (net (code "67") (name "Net-(U5-AN)") (class "Default")
      (node (ref "R6") (pin "2") (pinfunction "2_2") (pintype "unspecified"))
      (node (ref "U5") (pin "1") (pinfunction "AN_1") (pintype "unspecified"))
    )
    (net (code "68") (name "Net-(U7-AN)") (class "Default")
      (node (ref "R9") (pin "2") (pinfunction "2_2") (pintype "unspecified"))
      (node (ref "U7") (pin "1") (pinfunction "AN_1") (pintype "unspecified"))
    )
    (net (code "69") (name "Net-(U9-AN)") (class "Default")
      (node (ref "R12") (pin "2") (pinfunction "2_2") (pintype "unspecified"))
      (node (ref "U9") (pin "1") (pinfunction "AN_1") (pintype "unspecified"))
    )
    (net (code "70") (name "Net-(U11-AN)") (class "Default")
      (node (ref "R15") (pin "2") (pinfunction "2_2") (pintype "unspecified"))
      (node (ref "U11") (pin "1") (pinfunction "AN_1") (pintype "unspecified"))
    )
    (net (code "71") (name "Net-(U13-AN)") (class "Default")
      (node (ref "R18") (pin "2") (pinfunction "2_2") (pintype "unspecified"))
      (node (ref "U13") (pin "1") (pinfunction "AN_1") (pintype "unspecified"))
    )
    (net (code "72") (name "Net-(U15-AN)") (class "Default")
      (node (ref "R21") (pin "2") (pinfunction "2_2") (pintype "unspecified"))
      (node (ref "U15") (pin "1") (pinfunction "AN_1") (pintype "unspecified"))
    )
    (net (code "73") (name "Net-(U17-AN)") (class "Default")
      (node (ref "R24") (pin "2") (pinfunction "2_2") (pintype "unspecified"))
      (node (ref "U17") (pin "1") (pinfunction "AN_1") (pintype "unspecified"))
    )
    (net (code "74") (name "Net-(U19-AN)") (class "Default")
      (node (ref "R27") (pin "2") (pinfunction "2_2") (pintype "unspecified"))
      (node (ref "U19") (pin "1") (pinfunction "AN_1") (pintype "unspecified"))
    )
    (net (code "75") (name "SCL") (class "Default")
      (node (ref "U34") (pin "32") (pinfunction "D21_32") (pintype "unspecified"))
      (node (ref "X1") (pin "4") (pinfunction "SCL_4") (pintype "unspecified"))
    )
    (net (code "76") (name "SDA") (class "Default")
      (node (ref "U34") (pin "31") (pinfunction "D20_31") (pintype "unspecified"))
      (node (ref "X1") (pin "3") (pinfunction "SDA_3") (pintype "unspecified"))
    )
    (net (code "77") (name "T_1") (class "Default")
      (node (ref "U24") (pin "2") (pinfunction "TRIG_2") (pintype "input"))
      (node (ref "U33") (pin "3") (pinfunction "3_3") (pintype "unspecified"))
      (node (ref "U34") (pin "29") (pinfunction "D18_29") (pintype "unspecified"))
      (node (ref "U35") (pin "3") (pinfunction "3_3") (pintype "unspecified"))
    )
    (net (code "78") (name "T_2") (class "Default")
      (node (ref "U25") (pin "2") (pinfunction "TRIG_2") (pintype "input"))
      (node (ref "U33") (pin "7") (pinfunction "7_7") (pintype "unspecified"))
      (node (ref "U34") (pin "27") (pinfunction "D16_27") (pintype "unspecified"))
      (node (ref "U35") (pin "7") (pinfunction "7_7") (pintype "unspecified"))
    )
    (net (code "79") (name "T_3") (class "Default")
      (node (ref "U26") (pin "2") (pinfunction "TRIG_2") (pintype "input"))
      (node (ref "U33") (pin "11") (pinfunction "11_11") (pintype "unspecified"))
      (node (ref "U34") (pin "22") (pinfunction "D11_22") (pintype "unspecified"))
      (node (ref "U35") (pin "11") (pinfunction "11_11") (pintype "unspecified"))
    )
    (net (code "80") (name "T_4") (class "Default")
      (node (ref "U27") (pin "2") (pinfunction "TRIG_2") (pintype "input"))
      (node (ref "U33") (pin "15") (pinfunction "15_15") (pintype "unspecified"))
      (node (ref "U34") (pin "18") (pinfunction "D7_18") (pintype "unspecified"))
      (node (ref "U35") (pin "15") (pinfunction "15_15") (pintype "unspecified"))
    )
    (net (code "81") (name "T_5") (class "Default")
      (node (ref "U28") (pin "2") (pinfunction "TRIG_2") (pintype "input"))
      (node (ref "U33") (pin "19") (pinfunction "19_19") (pintype "unspecified"))
      (node (ref "U34") (pin "14") (pinfunction "D3_14") (pintype "unspecified"))
      (node (ref "U35") (pin "19") (pinfunction "19_19") (pintype "unspecified"))
    )
    (net (code "82") (name "T_6") (class "Default")
      (node (ref "U29") (pin "2") (pinfunction "TRIG_2") (pintype "input"))
      (node (ref "U33") (pin "18") (pinfunction "18_18") (pintype "unspecified"))
      (node (ref "U34") (pin "76") (pinfunction "D49_76") (pintype "unspecified"))
      (node (ref "U35") (pin "18") (pinfunction "18_18") (pintype "unspecified"))
    )
    (net (code "83") (name "T_7") (class "Default")
      (node (ref "U30") (pin "2") (pinfunction "TRIG_2") (pintype "input"))
      (node (ref "U33") (pin "14") (pinfunction "14_14") (pintype "unspecified"))
      (node (ref "U34") (pin "70") (pinfunction "D43_70") (pintype "unspecified"))
      (node (ref "U35") (pin "14") (pinfunction "14_14") (pintype "unspecified"))
    )
    (net (code "84") (name "T_8") (class "Default")
      (node (ref "U31") (pin "2") (pinfunction "TRIG_2") (pintype "input"))
      (node (ref "U33") (pin "10") (pinfunction "10_10") (pintype "unspecified"))
      (node (ref "U34") (pin "66") (pinfunction "D39_66") (pintype "unspecified"))
      (node (ref "U35") (pin "10") (pinfunction "10_10") (pintype "unspecified"))
    )
    (net (code "85") (name "T_9") (class "Default")
      (node (ref "U32") (pin "2") (pinfunction "TRIG_2") (pintype "input"))
      (node (ref "U33") (pin "6") (pinfunction "6_6") (pintype "unspecified"))
      (node (ref "U34") (pin "62") (pinfunction "D35_62") (pintype "unspecified"))
      (node (ref "U35") (pin "6") (pinfunction "6_6") (pintype "unspecified"))
    )
    (net (code "86") (name "VCC") (class "Default")
      (node (ref "U33") (pin "1") (pinfunction "1_1") (pintype "unspecified"))
      (node (ref "U34") (pin "5") (pinfunction "5V_5") (pintype "unspecified"))
      (node (ref "U34") (pin "6") (pinfunction "5V_6") (pintype "unspecified"))
      (node (ref "U35") (pin "1") (pinfunction "1_1") (pintype "unspecified"))
      (node (ref "X1") (pin "2") (pinfunction "VCC_2") (pintype "unspecified"))
    )
    (net (code "87") (name "unconnected-(U2-NC-Pad3)") (class "Default")
      (node (ref "U2") (pin "3") (pinfunction "NC_3") (pintype "unspecified"))
    )
    (net (code "88") (name "unconnected-(U2-NC-Pad5)") (class "Default")
      (node (ref "U2") (pin "5") (pinfunction "NC_5") (pintype "unspecified"))
    )
    (net (code "89") (name "unconnected-(U5-NC-Pad3)") (class "Default")
      (node (ref "U5") (pin "3") (pinfunction "NC_3") (pintype "unspecified"))
    )
    (net (code "90") (name "unconnected-(U5-NC-Pad5)") (class "Default")
      (node (ref "U5") (pin "5") (pinfunction "NC_5") (pintype "unspecified"))
    )
    (net (code "91") (name "unconnected-(U7-NC-Pad3)") (class "Default")
      (node (ref "U7") (pin "3") (pinfunction "NC_3") (pintype "unspecified"))
    )
    (net (code "92") (name "unconnected-(U7-NC-Pad5)") (class "Default")
      (node (ref "U7") (pin "5") (pinfunction "NC_5") (pintype "unspecified"))
    )
    (net (code "93") (name "unconnected-(U9-NC-Pad3)") (class "Default")
      (node (ref "U9") (pin "3") (pinfunction "NC_3") (pintype "unspecified"))
    )
    (net (code "94") (name "unconnected-(U9-NC-Pad5)") (class "Default")
      (node (ref "U9") (pin "5") (pinfunction "NC_5") (pintype "unspecified"))
    )
    (net (code "95") (name "unconnected-(U11-NC-Pad3)") (class "Default")
      (node (ref "U11") (pin "3") (pinfunction "NC_3") (pintype "unspecified"))
    )
    (net (code "96") (name "unconnected-(U11-NC-Pad5)") (class "Default")
      (node (ref "U11") (pin "5") (pinfunction "NC_5") (pintype "unspecified"))
    )
    (net (code "97") (name "unconnected-(U13-NC-Pad3)") (class "Default")
      (node (ref "U13") (pin "3") (pinfunction "NC_3") (pintype "unspecified"))
    )
    (net (code "98") (name "unconnected-(U13-NC-Pad5)") (class "Default")
      (node (ref "U13") (pin "5") (pinfunction "NC_5") (pintype "unspecified"))
    )
    (net (code "99") (name "unconnected-(U15-NC-Pad3)") (class "Default")
      (node (ref "U15") (pin "3") (pinfunction "NC_3") (pintype "unspecified"))
    )
    (net (code "100") (name "unconnected-(U15-NC-Pad5)") (class "Default")
      (node (ref "U15") (pin "5") (pinfunction "NC_5") (pintype "unspecified"))
    )
    (net (code "101") (name "unconnected-(U17-NC-Pad3)") (class "Default")
      (node (ref "U17") (pin "3") (pinfunction "NC_3") (pintype "unspecified"))
    )
    (net (code "102") (name "unconnected-(U17-NC-Pad5)") (class "Default")
      (node (ref "U17") (pin "5") (pinfunction "NC_5") (pintype "unspecified"))
    )
    (net (code "103") (name "unconnected-(U19-NC-Pad3)") (class "Default")
      (node (ref "U19") (pin "3") (pinfunction "NC_3") (pintype "unspecified"))
    )
    (net (code "104") (name "unconnected-(U19-NC-Pad5)") (class "Default")
      (node (ref "U19") (pin "5") (pinfunction "NC_5") (pintype "unspecified"))
    )
    (net (code "105") (name "unconnected-(U34-3.3V-Pad7)") (class "Default")
      (node (ref "U34") (pin "7") (pinfunction "3.3V_7") (pintype "unspecified"))
    )
    (net (code "106") (name "unconnected-(U34-3.3V-Pad8)") (class "Default")
      (node (ref "U34") (pin "8") (pinfunction "3.3V_8") (pintype "unspecified"))
    )
    (net (code "107") (name "unconnected-(U34-5V-Pad81)") (class "Default")
      (node (ref "U34") (pin "81") (pinfunction "5V_81") (pintype "unspecified"))
    )
    (net (code "108") (name "unconnected-(U34-A0-Pad43)") (class "Default")
      (node (ref "U34") (pin "43") (pinfunction "A0_43") (pintype "unspecified"))
    )
    (net (code "109") (name "unconnected-(U34-A1-Pad44)") (class "Default")
      (node (ref "U34") (pin "44") (pinfunction "A1_44") (pintype "unspecified"))
    )
    (net (code "110") (name "unconnected-(U34-A2-Pad45)") (class "Default")
      (node (ref "U34") (pin "45") (pinfunction "A2_45") (pintype "unspecified"))
    )
    (net (code "111") (name "unconnected-(U34-A3-Pad46)") (class "Default")
      (node (ref "U34") (pin "46") (pinfunction "A3_46") (pintype "unspecified"))
    )
    (net (code "112") (name "unconnected-(U34-A4-Pad47)") (class "Default")
      (node (ref "U34") (pin "47") (pinfunction "A4_47") (pintype "unspecified"))
    )
    (net (code "113") (name "unconnected-(U34-A5-Pad48)") (class "Default")
      (node (ref "U34") (pin "48") (pinfunction "A5_48") (pintype "unspecified"))
    )
    (net (code "114") (name "unconnected-(U34-A6-Pad49)") (class "Default")
      (node (ref "U34") (pin "49") (pinfunction "A6_49") (pintype "unspecified"))
    )
    (net (code "115") (name "unconnected-(U34-A7-Pad50)") (class "Default")
      (node (ref "U34") (pin "50") (pinfunction "A7_50") (pintype "unspecified"))
    )
    (net (code "116") (name "unconnected-(U34-A8-Pad51)") (class "Default")
      (node (ref "U34") (pin "51") (pinfunction "A8_51") (pintype "unspecified"))
    )
    (net (code "117") (name "unconnected-(U34-A9-Pad52)") (class "Default")
      (node (ref "U34") (pin "52") (pinfunction "A9_52") (pintype "unspecified"))
    )
    (net (code "118") (name "unconnected-(U34-A10-Pad53)") (class "Default")
      (node (ref "U34") (pin "53") (pinfunction "A10_53") (pintype "unspecified"))
    )
    (net (code "119") (name "unconnected-(U34-A11-Pad54)") (class "Default")
      (node (ref "U34") (pin "54") (pinfunction "A11_54") (pintype "unspecified"))
    )
    (net (code "120") (name "unconnected-(U34-A12-Pad55)") (class "Default")
      (node (ref "U34") (pin "55") (pinfunction "A12_55") (pintype "unspecified"))
    )
    (net (code "121") (name "unconnected-(U34-A13-Pad56)") (class "Default")
      (node (ref "U34") (pin "56") (pinfunction "A13_56") (pintype "unspecified"))
    )
    (net (code "122") (name "unconnected-(U34-A14-Pad57)") (class "Default")
      (node (ref "U34") (pin "57") (pinfunction "A14_57") (pintype "unspecified"))
    )
    (net (code "123") (name "unconnected-(U34-A15-Pad58)") (class "Default")
      (node (ref "U34") (pin "58") (pinfunction "A15_58") (pintype "unspecified"))
    )
    (net (code "124") (name "unconnected-(U34-AREF-Pad9)") (class "Default")
      (node (ref "U34") (pin "9") (pinfunction "AREF_9") (pintype "unspecified"))
    )
    (net (code "125") (name "unconnected-(U34-D2-Pad13)") (class "Default")
      (node (ref "U34") (pin "13") (pinfunction "D2_13") (pintype "unspecified"))
    )
    (net (code "126") (name "unconnected-(U34-D4-Pad15)") (class "Default")
      (node (ref "U34") (pin "15") (pinfunction "D4_15") (pintype "unspecified"))
    )
    (net (code "127") (name "unconnected-(U34-D6-Pad17)") (class "Default")
      (node (ref "U34") (pin "17") (pinfunction "D6_17") (pintype "unspecified"))
    )
    (net (code "128") (name "unconnected-(U34-D8-Pad19)") (class "Default")
      (node (ref "U34") (pin "19") (pinfunction "D8_19") (pintype "unspecified"))
    )
    (net (code "129") (name "unconnected-(U34-D10-Pad21)") (class "Default")
      (node (ref "U34") (pin "21") (pinfunction "D10_21") (pintype "unspecified"))
    )
    (net (code "130") (name "unconnected-(U34-D13-Pad24)") (class "Default")
      (node (ref "U34") (pin "24") (pinfunction "D13_24") (pintype "unspecified"))
    )
    (net (code "131") (name "unconnected-(U34-D14-Pad25)") (class "Default")
      (node (ref "U34") (pin "25") (pinfunction "D14_25") (pintype "unspecified"))
    )
    (net (code "132") (name "unconnected-(U34-D15-Pad26)") (class "Default")
      (node (ref "U34") (pin "26") (pinfunction "D15_26") (pintype "unspecified"))
    )
    (net (code "133") (name "unconnected-(U34-D19-Pad30)") (class "Default")
      (node (ref "U34") (pin "30") (pinfunction "D19_30") (pintype "unspecified"))
    )
    (net (code "134") (name "unconnected-(U34-D22-Pad33)") (class "Default")
      (node (ref "U34") (pin "33") (pinfunction "D22_33") (pintype "unspecified"))
    )
    (net (code "135") (name "unconnected-(U34-D23-Pad34)") (class "Default")
      (node (ref "U34") (pin "34") (pinfunction "D23_34") (pintype "unspecified"))
    )
    (net (code "136") (name "unconnected-(U34-D24-Pad35)") (class "Default")
      (node (ref "U34") (pin "35") (pinfunction "D24_35") (pintype "unspecified"))
    )
    (net (code "137") (name "unconnected-(U34-D25-Pad36)") (class "Default")
      (node (ref "U34") (pin "36") (pinfunction "D25_36") (pintype "unspecified"))
    )
    (net (code "138") (name "unconnected-(U34-D26-Pad37)") (class "Default")
      (node (ref "U34") (pin "37") (pinfunction "D26_37") (pintype "unspecified"))
    )
    (net (code "139") (name "unconnected-(U34-D27-Pad38)") (class "Default")
      (node (ref "U34") (pin "38") (pinfunction "D27_38") (pintype "unspecified"))
    )
    (net (code "140") (name "unconnected-(U34-D28-Pad39)") (class "Default")
      (node (ref "U34") (pin "39") (pinfunction "D28_39") (pintype "unspecified"))
    )
    (net (code "141") (name "unconnected-(U34-D29-Pad40)") (class "Default")
      (node (ref "U34") (pin "40") (pinfunction "D29_40") (pintype "unspecified"))
    )
    (net (code "142") (name "unconnected-(U34-GND-Pad85)") (class "Default")
      (node (ref "U34") (pin "85") (pinfunction "GND_85") (pintype "unspecified"))
    )
    (net (code "143") (name "unconnected-(U34-MISO-Pad82)") (class "Default")
      (node (ref "U34") (pin "82") (pinfunction "MISO_82") (pintype "unspecified"))
    )
    (net (code "144") (name "unconnected-(U34-MOSI-Pad83)") (class "Default")
      (node (ref "U34") (pin "83") (pinfunction "MOSI_83") (pintype "unspecified"))
    )
    (net (code "145") (name "unconnected-(U34-RSC-Pad86)") (class "Default")
      (node (ref "U34") (pin "86") (pinfunction "RSC_86") (pintype "unspecified"))
    )
    (net (code "146") (name "unconnected-(U34-RST-Pad10)") (class "Default")
      (node (ref "U34") (pin "10") (pinfunction "RST_10") (pintype "unspecified"))
    )
    (net (code "147") (name "unconnected-(U34-RX-Pad11)") (class "Default")
      (node (ref "U34") (pin "11") (pinfunction "RX_11") (pintype "unspecified"))
    )
    (net (code "148") (name "unconnected-(U34-SCK-Pad84)") (class "Default")
      (node (ref "U34") (pin "84") (pinfunction "SCK_84") (pintype "unspecified"))
    )
    (net (code "149") (name "unconnected-(U34-TX-Pad12)") (class "Default")
      (node (ref "U34") (pin "12") (pinfunction "TX_12") (pintype "unspecified"))
    )
  )
)
